# tinyPipes-proto.net
KiCad netlist of a schematic drawn in EAGLE
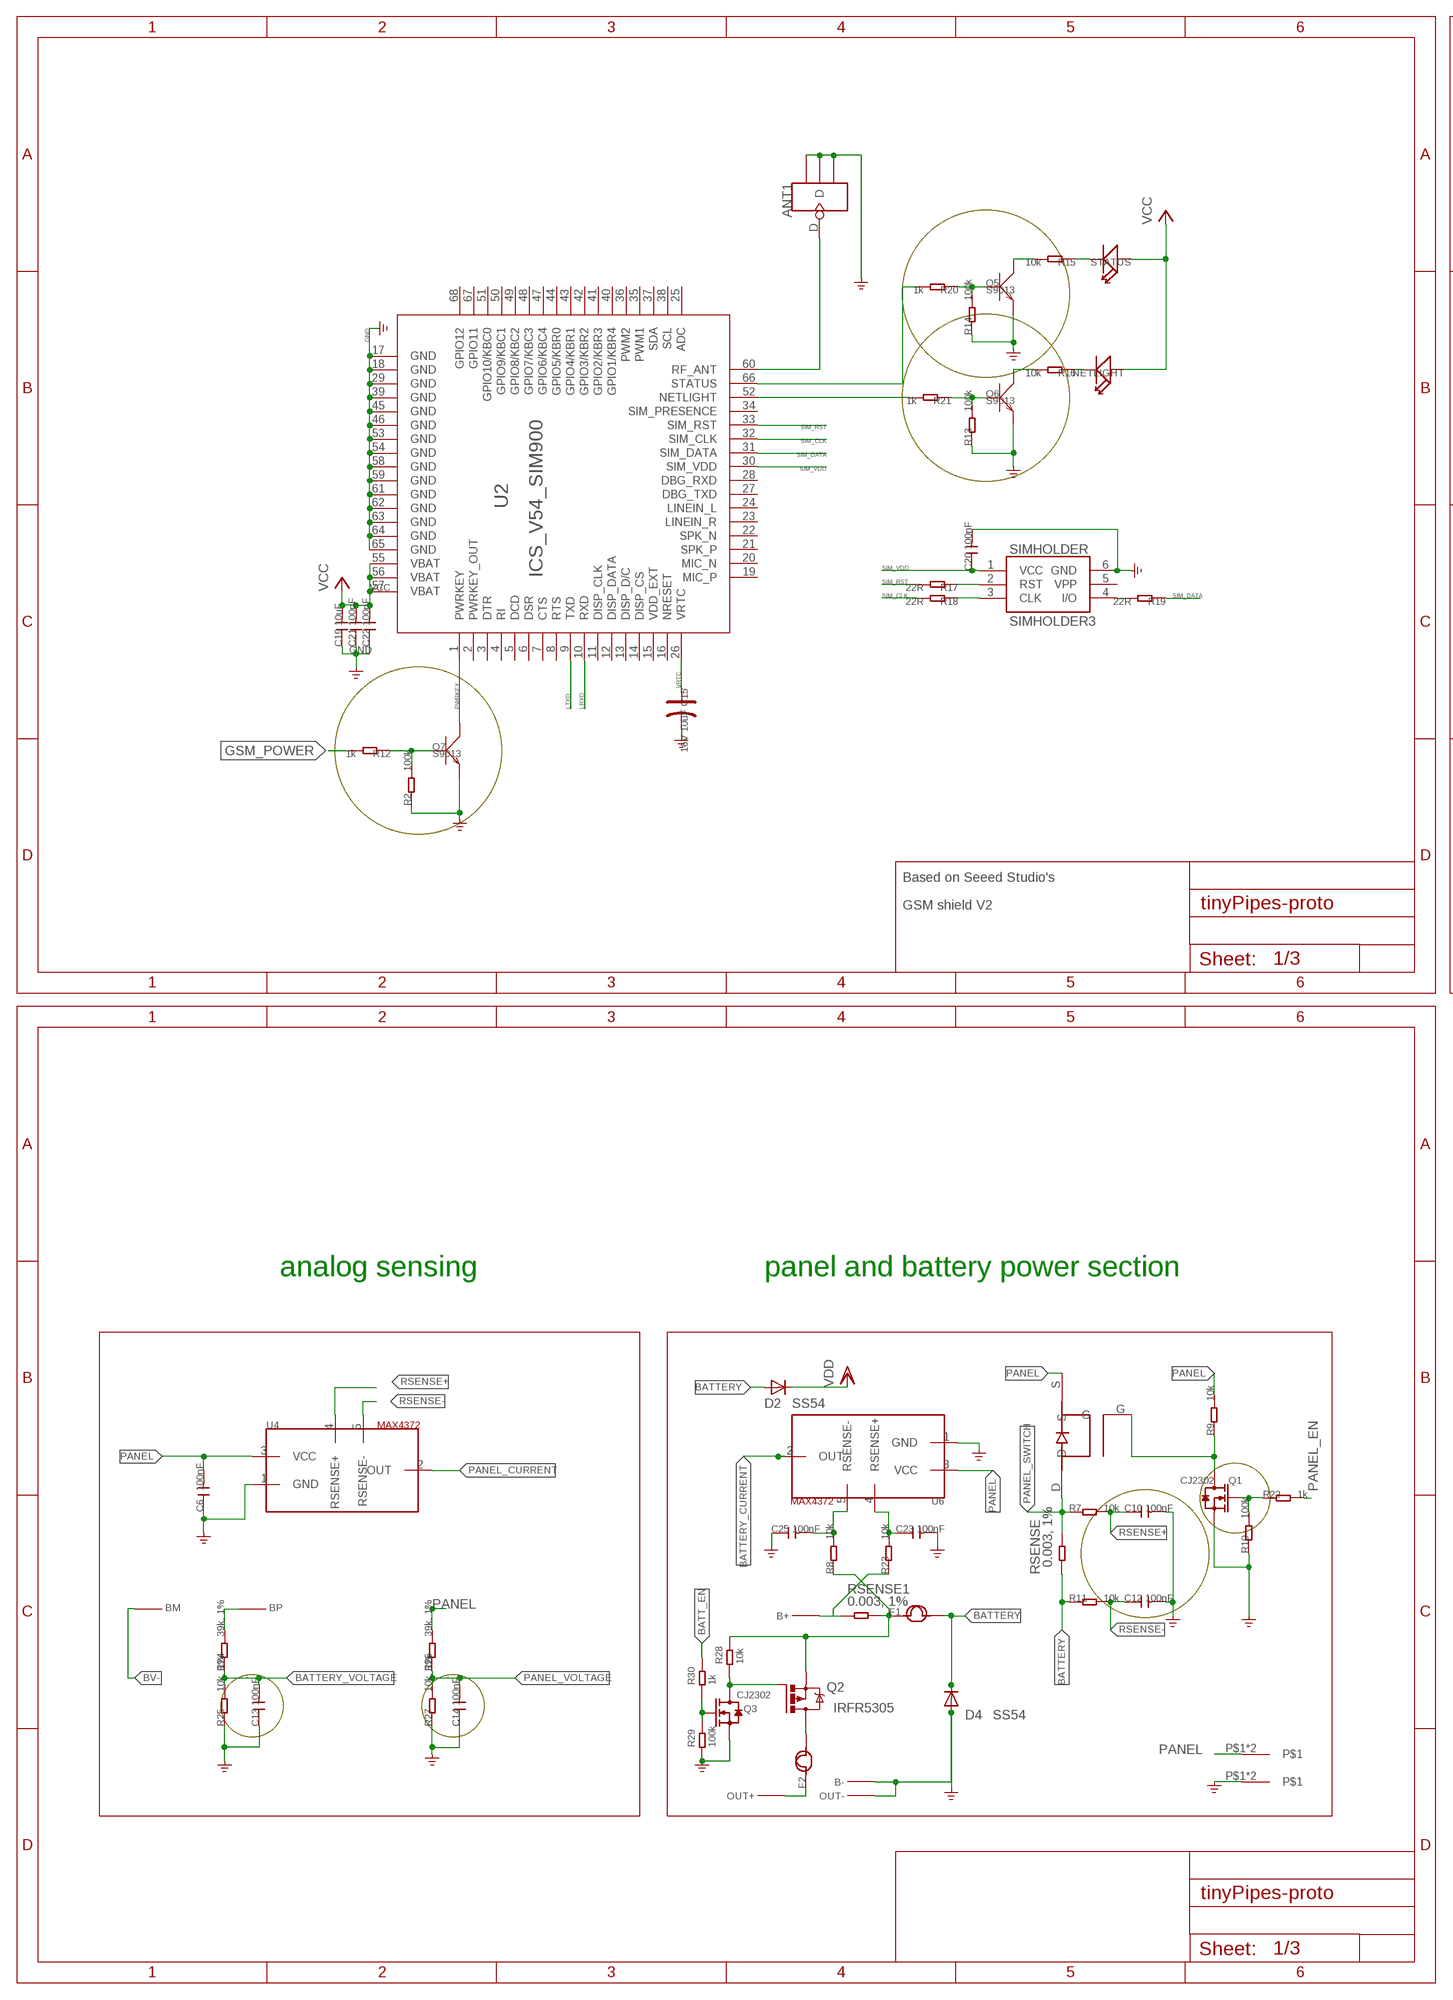
[diagram p0: schematic, sheet 1, part 1 of 2]
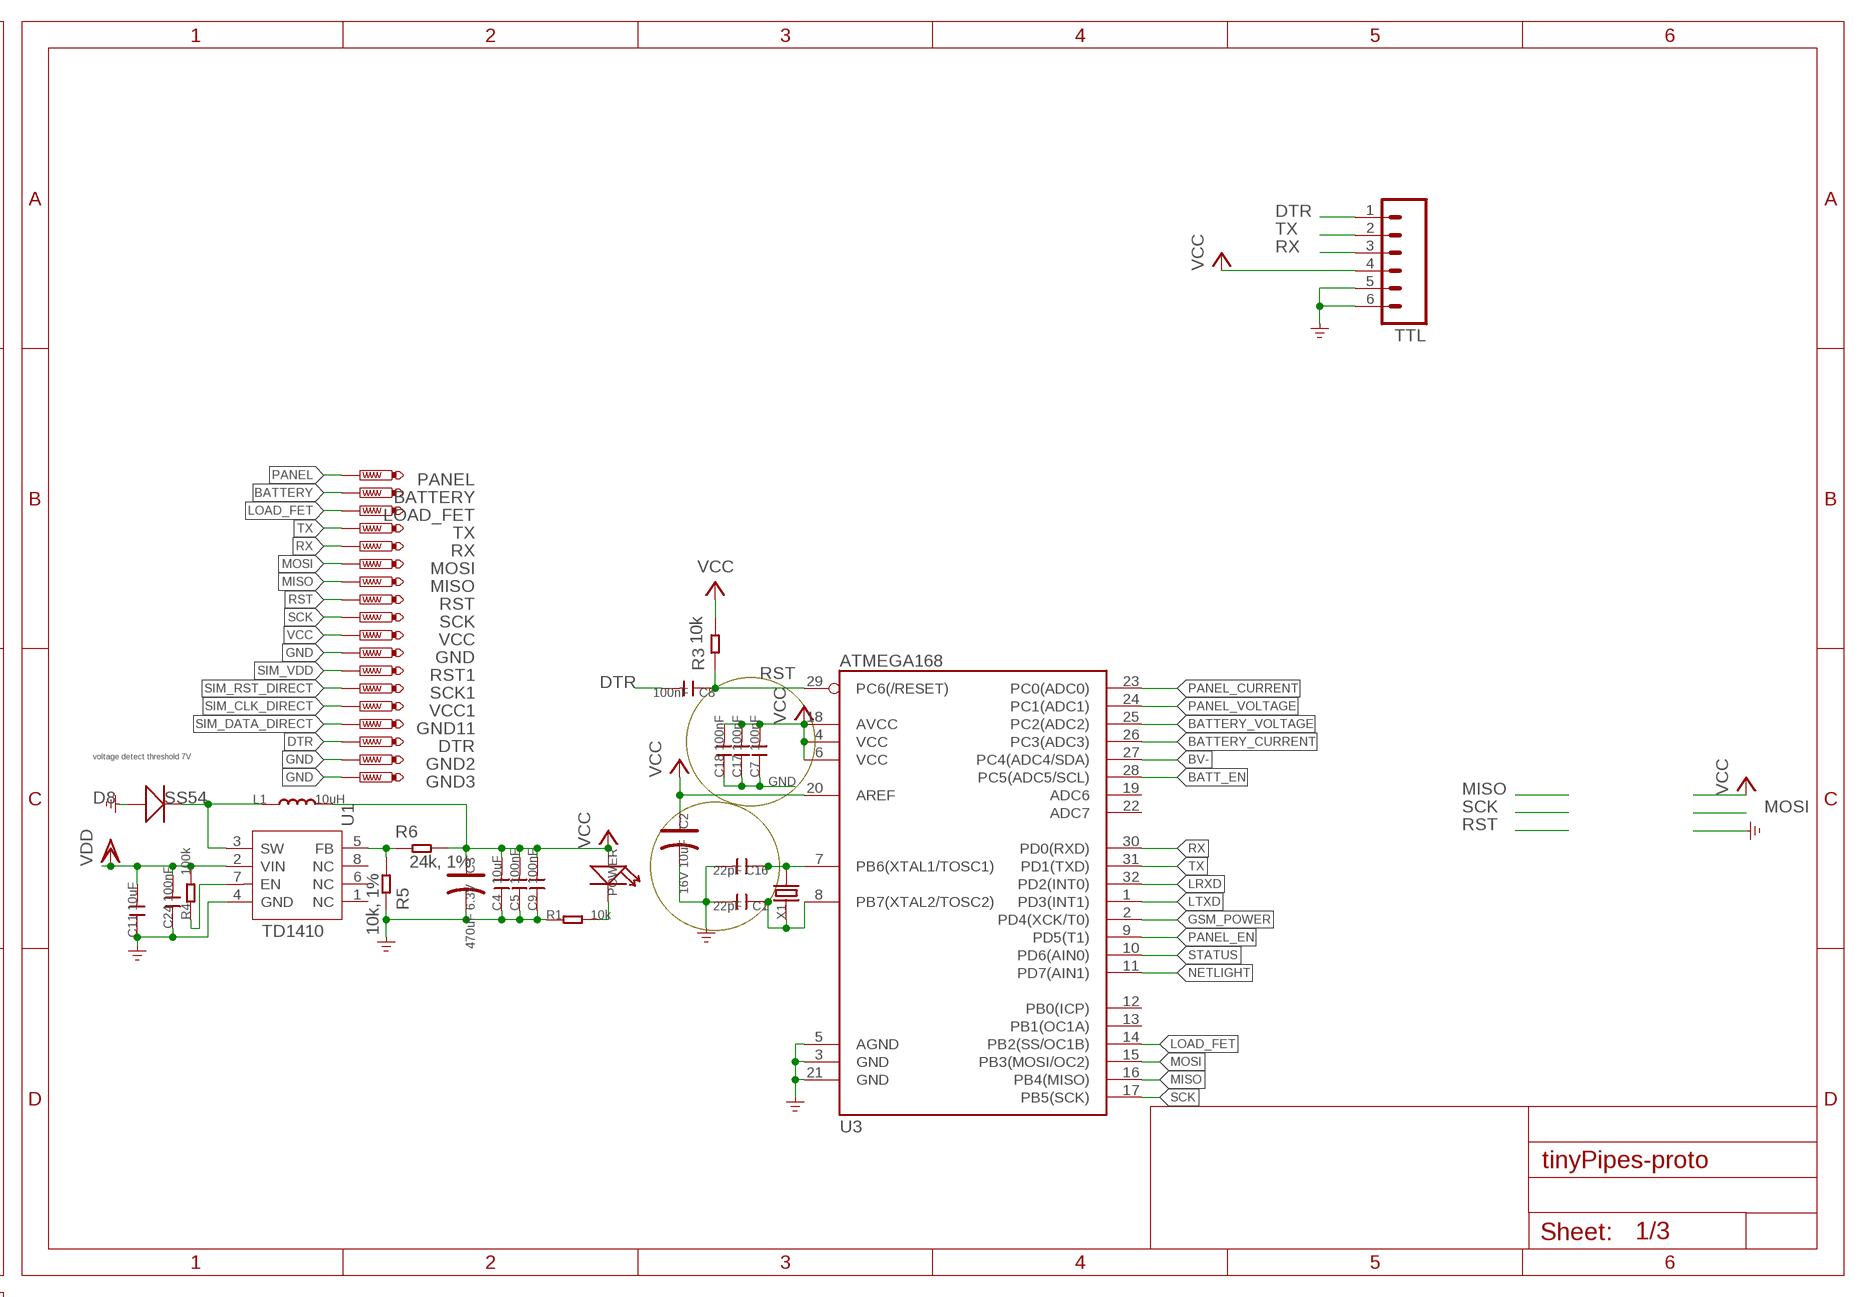
[diagram p1: schematic, sheet 1, part 2 of 2]

(export (version "E")
  (design (tool "Eeschema 10.0.6"))
  (components
    (comp (ref "ANT1")
      (value "ANTENNA-U-FL")
      (footprint "eagle-import:4P-U-FL")
      (libsource (lib "eagle-import") (part "ANTENNA-U-FL"))
    )
    (comp (ref "B+")
      (value "TINYPIPES_BATTBATT")
      (footprint "eagle-import:TINYPIPES_BATT")
      (libsource (lib "eagle-import") (part "TINYPIPES_BATTBATT"))
    )
    (comp (ref "B-")
      (value "TINYPIPES_BATTBATT")
      (footprint "eagle-import:TINYPIPES_BATT")
      (libsource (lib "eagle-import") (part "TINYPIPES_BATTBATT"))
    )
    (comp (ref "BATTERY")
      (value "PTR1B2,54")
      (footprint "eagle-import:B2,54")
      (libsource (lib "eagle-import") (part "PTR1B2,54"))
    )
    (comp (ref "BM")
      (value "TINYPIPES_BATTSBATT")
      (footprint "eagle-import:TINYPIPES_SBATT")
      (libsource (lib "eagle-import") (part "TINYPIPES_BATTSBATT"))
    )
    (comp (ref "BP")
      (value "TINYPIPES_BATTSBATT")
      (footprint "eagle-import:TINYPIPES_SBATT")
      (libsource (lib "eagle-import") (part "TINYPIPES_BATTSBATT"))
    )
    (comp (ref "C1")
      (value "22pF")
      (footprint "eagle-import:C0603")
      (libsource (lib "eagle-import") (part "C-0603"))
    )
    (comp (ref "C2")
      (value "16V 10uF")
      (footprint "eagle-import:AVX-A")
      (libsource (lib "eagle-import") (part "CAP-AVX-A"))
    )
    (comp (ref "C3")
      (value "470uF 6.3V")
      (footprint "eagle-import:AVX-D")
      (libsource (lib "eagle-import") (part "CAP-AVX-D"))
    )
    (comp (ref "C4")
      (value "10uF")
      (footprint "eagle-import:C0805")
      (libsource (lib "eagle-import") (part "C-0805"))
    )
    (comp (ref "C5")
      (value "100nF")
      (footprint "eagle-import:C0603")
      (libsource (lib "eagle-import") (part "C-0603"))
    )
    (comp (ref "C6")
      (value "100nF")
      (footprint "eagle-import:C0603")
      (libsource (lib "eagle-import") (part "C-0603"))
    )
    (comp (ref "C7")
      (value "100nF")
      (footprint "eagle-import:C0603")
      (libsource (lib "eagle-import") (part "C-0603"))
    )
    (comp (ref "C8")
      (value "100nF")
      (footprint "eagle-import:C0603")
      (libsource (lib "eagle-import") (part "C-0603"))
    )
    (comp (ref "C9")
      (value "100nF")
      (footprint "eagle-import:C0603")
      (libsource (lib "eagle-import") (part "C-0603"))
    )
    (comp (ref "C10")
      (value "100nF")
      (footprint "eagle-import:C0805")
      (libsource (lib "eagle-import") (part "C-0805"))
    )
    (comp (ref "C11")
      (value "10uF")
      (footprint "eagle-import:C0805")
      (libsource (lib "eagle-import") (part "C-0805"))
    )
    (comp (ref "C12")
      (value "100nF")
      (footprint "eagle-import:C0805")
      (libsource (lib "eagle-import") (part "C-0805"))
    )
    (comp (ref "C13")
      (value "100nF")
      (footprint "eagle-import:C0603")
      (libsource (lib "eagle-import") (part "C-0603"))
    )
    (comp (ref "C14")
      (value "100nF")
      (footprint "eagle-import:C0603")
      (libsource (lib "eagle-import") (part "C-0603"))
    )
    (comp (ref "C15")
      (value "16V 10uF")
      (footprint "eagle-import:AVX-A")
      (libsource (lib "eagle-import") (part "CAP-AVX-A"))
    )
    (comp (ref "C16")
      (value "22pF")
      (footprint "eagle-import:C0603")
      (libsource (lib "eagle-import") (part "C-0603"))
    )
    (comp (ref "C17")
      (value "100nF")
      (footprint "eagle-import:C0603")
      (libsource (lib "eagle-import") (part "C-0603"))
    )
    (comp (ref "C18")
      (value "100nF")
      (footprint "eagle-import:C0603")
      (libsource (lib "eagle-import") (part "C-0603"))
    )
    (comp (ref "C19")
      (value "10uF")
      (footprint "eagle-import:C0805")
      (libsource (lib "eagle-import") (part "C-0805"))
    )
    (comp (ref "C20")
      (value "100nF")
      (footprint "eagle-import:C0603")
      (libsource (lib "eagle-import") (part "C-0603"))
    )
    (comp (ref "C21")
      (value "100nF")
      (footprint "eagle-import:C0603")
      (libsource (lib "eagle-import") (part "C-0603"))
    )
    (comp (ref "C22")
      (value "100nF")
      (footprint "eagle-import:C0603")
      (libsource (lib "eagle-import") (part "C-0603"))
    )
    (comp (ref "C23")
      (value "100nF")
      (footprint "eagle-import:C0805")
      (libsource (lib "eagle-import") (part "C-0805"))
    )
    (comp (ref "C24")
      (value "100nF")
      (footprint "eagle-import:C0603")
      (libsource (lib "eagle-import") (part "C-0603"))
    )
    (comp (ref "C25")
      (value "100nF")
      (footprint "eagle-import:C0805")
      (libsource (lib "eagle-import") (part "C-0805"))
    )
    (comp (ref "D2")
      (value "SS54")
      (footprint "eagle-import:SMB")
      (libsource (lib "eagle-import") (part "DIODE-SMB"))
    )
    (comp (ref "D4")
      (value "SS54")
      (footprint "eagle-import:SMB")
      (libsource (lib "eagle-import") (part "DIODE-SMB"))
    )
    (comp (ref "D8")
      (value "SS54")
      (footprint "eagle-import:SMB")
      (libsource (lib "eagle-import") (part "D'MBRS240LT3'"))
    )
    (comp (ref "DTR")
      (value "PTR1B2,54")
      (footprint "eagle-import:B2,54")
      (libsource (lib "eagle-import") (part "PTR1B2,54"))
    )
    (comp (ref "F1")
      (value "FUSE16R700")
      (footprint "eagle-import:0210")
      (libsource (lib "eagle-import") (part "FUSE16R700"))
    )
    (comp (ref "F2")
      (value "FUSE16R700")
      (footprint "eagle-import:0210")
      (libsource (lib "eagle-import") (part "FUSE16R700"))
    )
    (comp (ref "GND")
      (value "PTR1B2,54")
      (footprint "eagle-import:B2,54")
      (libsource (lib "eagle-import") (part "PTR1B2,54"))
    )
    (comp (ref "GND2")
      (value "PTR1B2,54")
      (footprint "eagle-import:B2,54")
      (libsource (lib "eagle-import") (part "PTR1B2,54"))
    )
    (comp (ref "GND3")
      (value "PTR1B2,54")
      (footprint "eagle-import:B2,54")
      (libsource (lib "eagle-import") (part "PTR1B2,54"))
    )
    (comp (ref "GND11")
      (value "PTR1B2,54")
      (footprint "eagle-import:B2,54")
      (libsource (lib "eagle-import") (part "PTR1B2,54"))
    )
    (comp (ref "L1")
      (value "10uH")
      (footprint "eagle-import:L0630")
      (libsource (lib "eagle-import") (part "L'0630'"))
    )
    (comp (ref "LOAD_FET")
      (value "PTR1B2,54")
      (footprint "eagle-import:B2,54")
      (libsource (lib "eagle-import") (part "PTR1B2,54"))
    )
    (comp (ref "MISO")
      (value "PTR1B2,54")
      (footprint "eagle-import:B2,54")
      (libsource (lib "eagle-import") (part "PTR1B2,54"))
    )
    (comp (ref "MOSI")
      (value "PTR1B2,54")
      (footprint "eagle-import:B2,54")
      (libsource (lib "eagle-import") (part "PTR1B2,54"))
    )
    (comp (ref "NETLIGHT")
      (value "LED'0603'")
      (footprint "eagle-import:LED-0603")
      (libsource (lib "eagle-import") (part "LED'0603'"))
    )
    (comp (ref "OUT+")
      (value "TINYPIPES_BATTBATT")
      (footprint "eagle-import:TINYPIPES_BATT")
      (libsource (lib "eagle-import") (part "TINYPIPES_BATTBATT"))
    )
    (comp (ref "OUT-")
      (value "TINYPIPES_BATTBATT")
      (footprint "eagle-import:TINYPIPES_BATT")
      (libsource (lib "eagle-import") (part "TINYPIPES_BATTBATT"))
    )
    (comp (ref "PANEL")
      (value "PTR1B2,54")
      (footprint "eagle-import:B2,54")
      (libsource (lib "eagle-import") (part "PTR1B2,54"))
    )
    (comp (ref "PANEL+")
      (value "TINYPIPES_BATTPANEL")
      (footprint "eagle-import:TINYPIPES_PANEL")
      (libsource (lib "eagle-import") (part "tinyPipes_v2.5_TINYPIPES_BATTPANEL"))
    )
    (comp (ref "PANEL-")
      (value "TINYPIPES_BATTPANEL")
      (footprint "eagle-import:TINYPIPES_PANEL")
      (libsource (lib "eagle-import") (part "tinyPipes_v2.5_TINYPIPES_BATTPANEL"))
    )
    (comp (ref "POWER")
      (value "LED'0603'")
      (footprint "eagle-import:LED-0603")
      (libsource (lib "eagle-import") (part "LED'0603'"))
    )
    (comp (ref "Q1")
      (value "CJ2302")
      (footprint "eagle-import:SOT23")
      (libsource (lib "eagle-import") (part "MOSFET-N'SOT23'"))
    )
    (comp (ref "Q2")
      (value "IRFR5305")
      (footprint "eagle-import:D-PAK_TO252AA")
      (libsource (lib "eagle-import") (part "IRF?5305R"))
    )
    (comp (ref "Q3")
      (value "CJ2302")
      (footprint "eagle-import:SOT23")
      (libsource (lib "eagle-import") (part "MOSFET-N'SOT23'"))
    )
    (comp (ref "Q5")
      (value "S9013")
      (footprint "eagle-import:SOT23")
      (libsource (lib "eagle-import") (part "TRANSISTOR-NPN-SOT23"))
    )
    (comp (ref "Q6")
      (value "S9013")
      (footprint "eagle-import:SOT23")
      (libsource (lib "eagle-import") (part "TRANSISTOR-NPN-SOT23"))
    )
    (comp (ref "Q7")
      (value "S9013")
      (footprint "eagle-import:SOT23")
      (libsource (lib "eagle-import") (part "TRANSISTOR-NPN-SOT23"))
    )
    (comp (ref "R1")
      (value "10k")
      (footprint "eagle-import:R0603")
      (libsource (lib "eagle-import") (part "R-0603"))
    )
    (comp (ref "R2")
      (value "100k")
      (footprint "eagle-import:R0603")
      (libsource (lib "eagle-import") (part "R-0603"))
    )
    (comp (ref "R3")
      (value "10k")
      (footprint "eagle-import:R0603")
      (libsource (lib "eagle-import") (part "R-0603"))
    )
    (comp (ref "R4")
      (value "100k")
      (footprint "eagle-import:R0603")
      (libsource (lib "eagle-import") (part "R-0603"))
    )
    (comp (ref "R5")
      (value "10k, 1%")
      (footprint "eagle-import:R0603")
      (libsource (lib "eagle-import") (part "R-0603"))
    )
    (comp (ref "R6")
      (value "24k, 1%")
      (footprint "eagle-import:R0603")
      (libsource (lib "eagle-import") (part "R-0603"))
    )
    (comp (ref "R7")
      (value "10k")
      (footprint "eagle-import:R0603")
      (libsource (lib "eagle-import") (part "R-0603"))
    )
    (comp (ref "R8")
      (value "10k")
      (footprint "eagle-import:R0603")
      (libsource (lib "eagle-import") (part "R-0603"))
    )
    (comp (ref "R9")
      (value "10k")
      (footprint "eagle-import:R0603")
      (libsource (lib "eagle-import") (part "R-0603"))
    )
    (comp (ref "R10")
      (value "100k")
      (footprint "eagle-import:R0603")
      (libsource (lib "eagle-import") (part "R-0603"))
    )
    (comp (ref "R11")
      (value "10k")
      (footprint "eagle-import:R0603")
      (libsource (lib "eagle-import") (part "R-0603"))
    )
    (comp (ref "R12")
      (value "1k")
      (footprint "eagle-import:R0603")
      (libsource (lib "eagle-import") (part "R-0603"))
    )
    (comp (ref "R13")
      (value "100k")
      (footprint "eagle-import:R0603")
      (libsource (lib "eagle-import") (part "R-0603"))
    )
    (comp (ref "R14")
      (value "100k")
      (footprint "eagle-import:R0603")
      (libsource (lib "eagle-import") (part "R-0603"))
    )
    (comp (ref "R15")
      (value "10k")
      (footprint "eagle-import:R0603")
      (libsource (lib "eagle-import") (part "R-0603"))
    )
    (comp (ref "R16")
      (value "10k")
      (footprint "eagle-import:R0603")
      (libsource (lib "eagle-import") (part "R-0603"))
    )
    (comp (ref "R17")
      (value "22R")
      (footprint "eagle-import:R0603")
      (libsource (lib "eagle-import") (part "R-0603"))
    )
    (comp (ref "R18")
      (value "22R")
      (footprint "eagle-import:R0603")
      (libsource (lib "eagle-import") (part "R-0603"))
    )
    (comp (ref "R19")
      (value "22R")
      (footprint "eagle-import:R0603")
      (libsource (lib "eagle-import") (part "R-0603"))
    )
    (comp (ref "R20")
      (value "1k")
      (footprint "eagle-import:R0603")
      (libsource (lib "eagle-import") (part "R-0603"))
    )
    (comp (ref "R21")
      (value "1k")
      (footprint "eagle-import:R0603")
      (libsource (lib "eagle-import") (part "R-0603"))
    )
    (comp (ref "R22")
      (value "1k")
      (footprint "eagle-import:R0603")
      (libsource (lib "eagle-import") (part "R-0603"))
    )
    (comp (ref "R23")
      (value "10k")
      (footprint "eagle-import:R0603")
      (libsource (lib "eagle-import") (part "R-0603"))
    )
    (comp (ref "R24")
      (value "39k, 1%")
      (footprint "eagle-import:R0603")
      (libsource (lib "eagle-import") (part "R-0603"))
    )
    (comp (ref "R25")
      (value "10k, 1%")
      (footprint "eagle-import:R0603")
      (libsource (lib "eagle-import") (part "R-0603"))
    )
    (comp (ref "R26")
      (value "39k, 1%")
      (footprint "eagle-import:R0603")
      (libsource (lib "eagle-import") (part "R-0603"))
    )
    (comp (ref "R27")
      (value "10k, 1%")
      (footprint "eagle-import:R0603")
      (libsource (lib "eagle-import") (part "R-0603"))
    )
    (comp (ref "R28")
      (value "10k")
      (footprint "eagle-import:R0603")
      (libsource (lib "eagle-import") (part "R-0603"))
    )
    (comp (ref "R29")
      (value "100k")
      (footprint "eagle-import:R0603")
      (libsource (lib "eagle-import") (part "R-0603"))
    )
    (comp (ref "R30")
      (value "1k")
      (footprint "eagle-import:R0603")
      (libsource (lib "eagle-import") (part "R-0603"))
    )
    (comp (ref "RSENSE")
      (value "0.003, 1%")
      (footprint "eagle-import:R2512")
      (libsource (lib "eagle-import") (part "R-2512"))
    )
    (comp (ref "RSENSE1")
      (value "0.003, 1%")
      (footprint "eagle-import:R2512")
      (libsource (lib "eagle-import") (part "R-2512"))
    )
    (comp (ref "RST")
      (value "PTR1B2,54")
      (footprint "eagle-import:B2,54")
      (libsource (lib "eagle-import") (part "PTR1B2,54"))
    )
    (comp (ref "RST1")
      (value "PTR1B2,54")
      (footprint "eagle-import:B2,54")
      (libsource (lib "eagle-import") (part "PTR1B2,54"))
    )
    (comp (ref "RX")
      (value "PTR1B2,54")
      (footprint "eagle-import:B2,54")
      (libsource (lib "eagle-import") (part "PTR1B2,54"))
    )
    (comp (ref "SCK")
      (value "PTR1B2,54")
      (footprint "eagle-import:B2,54")
      (libsource (lib "eagle-import") (part "PTR1B2,54"))
    )
    (comp (ref "SCK1")
      (value "PTR1B2,54")
      (footprint "eagle-import:B2,54")
      (libsource (lib "eagle-import") (part "PTR1B2,54"))
    )
    (comp (ref "SIMHOLDER")
      (value "SIMHOLDER3")
      (footprint "eagle-import:SIMHOLDER3")
      (libsource (lib "eagle-import") (part "SIMHOLDER3"))
    )
    (comp (ref "STATUS")
      (value "LED'0603'")
      (footprint "eagle-import:LED-0603")
      (libsource (lib "eagle-import") (part "LED'0603'"))
    )
    (comp (ref "TTL")
      (value "M06LOCK")
      (footprint "eagle-import:1X06_LOCK")
      (libsource (lib "eagle-import") (part "M06LOCK"))
    )
    (comp (ref "TX")
      (value "PTR1B2,54")
      (footprint "eagle-import:B2,54")
      (libsource (lib "eagle-import") (part "PTR1B2,54"))
    )
    (comp (ref "U1")
      (value "TD1410")
      (footprint "eagle-import:SOP8")
      (libsource (lib "eagle-import") (part "TD1410"))
    )
    (comp (ref "U2")
      (value "ICS_V54_SIM900")
      (footprint "eagle-import:ICS_V54_SIM900")
      (libsource (lib "eagle-import") (part "ICS_V54_SIM900"))
    )
    (comp (ref "U3")
      (value "ATMEGA168")
      (footprint "eagle-import:TQFP32-08")
      (libsource (lib "eagle-import") (part "ATMEGA168"))
    )
    (comp (ref "U4")
      (value "MAX4372")
      (footprint "eagle-import:SOT23-5")
      (libsource (lib "eagle-import") (part "MAX4372"))
    )
    (comp (ref "U5")
      (value "SI4435POWER")
      (footprint "eagle-import:SO8_FET")
      (libsource (lib "eagle-import") (part "SI4435POWER"))
    )
    (comp (ref "U6")
      (value "MAX4372")
      (footprint "eagle-import:SOT23-5")
      (libsource (lib "eagle-import") (part "MAX4372"))
    )
    (comp (ref "VCC")
      (value "PTR1B2,54")
      (footprint "eagle-import:B2,54")
      (libsource (lib "eagle-import") (part "PTR1B2,54"))
    )
    (comp (ref "VCC1")
      (value "PTR1B2,54")
      (footprint "eagle-import:B2,54")
      (libsource (lib "eagle-import") (part "PTR1B2,54"))
    )
    (comp (ref "X1")
      (value "CRYSTAL'5032'")
      (footprint "eagle-import:2P-SMD-5X3.2")
      (libsource (lib "eagle-import") (part "CRYSTAL'5032'"))
    )
  )
  (nets
    (net (code "1") (name "BATTERY") (class "Default")
      (node (ref "BATTERY") (pin "TP") (pinfunction "TP_TP") (pintype "input"))
      (node (ref "D2") (pin "A") (pinfunction "A_A") (pintype "passive"))
      (node (ref "D4") (pin "C") (pinfunction "C_C") (pintype "passive"))
      (node (ref "F1") (pin "2") (pinfunction "2_2") (pintype "bidirectional"))
      (node (ref "R11") (pin "1") (pinfunction "1_1") (pintype "passive"))
      (node (ref "RSENSE") (pin "1") (pinfunction "1_1") (pintype "passive"))
    )
    (net (code "2") (name "BATTERY_CURRENT") (class "Default")
      (node (ref "U3") (pin "26") (pinfunction "PC3(ADC3)_26") (pintype "bidirectional"))
      (node (ref "U6") (pin "2") (pinfunction "OUT_2") (pintype "bidirectional"))
    )
    (net (code "3") (name "BATTERY_VOLTAGE") (class "Default")
      (node (ref "C13") (pin "2") (pinfunction "2_2") (pintype "passive"))
      (node (ref "R24") (pin "1") (pinfunction "1_1") (pintype "passive"))
      (node (ref "R25") (pin "2") (pinfunction "2_2") (pintype "passive"))
      (node (ref "U3") (pin "25") (pinfunction "PC2(ADC2)_25") (pintype "bidirectional"))
    )
    (net (code "4") (name "BATT_EN") (class "Default")
      (node (ref "R30") (pin "2") (pinfunction "2_2") (pintype "passive"))
      (node (ref "U3") (pin "28") (pinfunction "PC5(ADC5/SCL)_28") (pintype "bidirectional"))
    )
    (net (code "5") (name "BV-") (class "Default")
      (node (ref "BM") (pin "P$1") (pinfunction "P$1_P$1") (pintype "bidirectional"))
      (node (ref "U3") (pin "27") (pinfunction "PC4(ADC4/SDA)_27") (pintype "bidirectional"))
    )
    (net (code "6") (name "DTR") (class "Default")
      (node (ref "C8") (pin "2") (pinfunction "2_2") (pintype "passive"))
      (node (ref "DTR") (pin "TP") (pinfunction "TP_TP") (pintype "input"))
      (node (ref "TTL") (pin "1") (pinfunction "1_1") (pintype "passive"))
    )
    (net (code "7") (name "GND") (class "Default")
      (node (ref "ANT1") (pin "GND1") (pinfunction "GND1_GND1") (pintype "bidirectional"))
      (node (ref "ANT1") (pin "GND2") (pinfunction "GND2_GND2") (pintype "bidirectional"))
      (node (ref "ANT1") (pin "GND3") (pinfunction "GND3_GND3") (pintype "bidirectional"))
      (node (ref "B-") (pin "1") (pinfunction "P$1_1") (pintype "bidirectional"))
      (node (ref "C1") (pin "2") (pinfunction "2_2") (pintype "passive"))
      (node (ref "C10") (pin "2") (pinfunction "2_2") (pintype "passive"))
      (node (ref "C11") (pin "1") (pinfunction "1_1") (pintype "passive"))
      (node (ref "C12") (pin "2") (pinfunction "2_2") (pintype "passive"))
      (node (ref "C13") (pin "1") (pinfunction "1_1") (pintype "passive"))
      (node (ref "C14") (pin "1") (pinfunction "1_1") (pintype "passive"))
      (node (ref "C15") (pin "-") (pinfunction "-_-") (pintype "passive"))
      (node (ref "C16") (pin "2") (pinfunction "2_2") (pintype "passive"))
      (node (ref "C17") (pin "1") (pinfunction "1_1") (pintype "passive"))
      (node (ref "C18") (pin "1") (pinfunction "1_1") (pintype "passive"))
      (node (ref "C19") (pin "1") (pinfunction "1_1") (pintype "passive"))
      (node (ref "C2") (pin "-") (pinfunction "-_-") (pintype "passive"))
      (node (ref "C20") (pin "2") (pinfunction "2_2") (pintype "passive"))
      (node (ref "C21") (pin "1") (pinfunction "1_1") (pintype "passive"))
      (node (ref "C22") (pin "1") (pinfunction "1_1") (pintype "passive"))
      (node (ref "C23") (pin "2") (pinfunction "2_2") (pintype "passive"))
      (node (ref "C24") (pin "1") (pinfunction "1_1") (pintype "passive"))
      (node (ref "C25") (pin "1") (pinfunction "1_1") (pintype "passive"))
      (node (ref "C3") (pin "-") (pinfunction "-_-") (pintype "passive"))
      (node (ref "C4") (pin "1") (pinfunction "1_1") (pintype "passive"))
      (node (ref "C5") (pin "1") (pinfunction "1_1") (pintype "passive"))
      (node (ref "C6") (pin "1") (pinfunction "1_1") (pintype "passive"))
      (node (ref "C7") (pin "1") (pinfunction "1_1") (pintype "passive"))
      (node (ref "C9") (pin "1") (pinfunction "1_1") (pintype "passive"))
      (node (ref "D4") (pin "A") (pinfunction "A_A") (pintype "passive"))
      (node (ref "D8") (pin "+") (pinfunction "+_+") (pintype "passive"))
      (node (ref "GND") (pin "TP") (pinfunction "TP_TP") (pintype "input"))
      (node (ref "GND2") (pin "TP") (pinfunction "TP_TP") (pintype "input"))
      (node (ref "GND3") (pin "TP") (pinfunction "TP_TP") (pintype "input"))
      (node (ref "OUT-") (pin "1") (pinfunction "P$1_1") (pintype "bidirectional"))
      (node (ref "PANEL-") (pin "P$1") (pinfunction "P$1_P$1") (pintype "bidirectional"))
      (node (ref "PANEL-") (pin "P$2") (pinfunction "P$1_P$2") (pintype "bidirectional"))
      (node (ref "Q1") (pin "2") (pinfunction "S_2") (pintype "passive"))
      (node (ref "Q3") (pin "2") (pinfunction "S_2") (pintype "passive"))
      (node (ref "Q5") (pin "2") (pinfunction "E_2") (pintype "passive"))
      (node (ref "Q6") (pin "2") (pinfunction "E_2") (pintype "passive"))
      (node (ref "Q7") (pin "2") (pinfunction "E_2") (pintype "passive"))
      (node (ref "R1") (pin "1") (pinfunction "1_1") (pintype "passive"))
      (node (ref "R10") (pin "1") (pinfunction "1_1") (pintype "passive"))
      (node (ref "R13") (pin "1") (pinfunction "1_1") (pintype "passive"))
      (node (ref "R14") (pin "1") (pinfunction "1_1") (pintype "passive"))
      (node (ref "R2") (pin "1") (pinfunction "1_1") (pintype "passive"))
      (node (ref "R25") (pin "1") (pinfunction "1_1") (pintype "passive"))
      (node (ref "R27") (pin "1") (pinfunction "1_1") (pintype "passive"))
      (node (ref "R29") (pin "1") (pinfunction "1_1") (pintype "passive"))
      (node (ref "R5") (pin "2") (pinfunction "2_2") (pintype "passive"))
      (node (ref "SIMHOLDER") (pin "6") (pinfunction "GND_6") (pintype "bidirectional"))
      (node (ref "TTL") (pin "5") (pinfunction "5_5") (pintype "passive"))
      (node (ref "TTL") (pin "6") (pinfunction "6_6") (pintype "passive"))
      (node (ref "U1") (pin "4") (pinfunction "GND_4") (pintype "power_in"))
      (node (ref "U2") (pin "17") (pinfunction "GND_17") (pintype "power_in"))
      (node (ref "U2") (pin "18") (pinfunction "GND_18") (pintype "power_in"))
      (node (ref "U2") (pin "29") (pinfunction "GND_29") (pintype "power_in"))
      (node (ref "U2") (pin "39") (pinfunction "GND_39") (pintype "power_in"))
      (node (ref "U2") (pin "45") (pinfunction "GND_45") (pintype "power_in"))
      (node (ref "U2") (pin "46") (pinfunction "GND_46") (pintype "power_in"))
      (node (ref "U2") (pin "53") (pinfunction "GND_53") (pintype "power_in"))
      (node (ref "U2") (pin "54") (pinfunction "GND_54") (pintype "power_in"))
      (node (ref "U2") (pin "58") (pinfunction "GND_58") (pintype "power_in"))
      (node (ref "U2") (pin "59") (pinfunction "GND_59") (pintype "power_in"))
      (node (ref "U2") (pin "61") (pinfunction "GND_61") (pintype "power_in"))
      (node (ref "U2") (pin "62") (pinfunction "GND_62") (pintype "power_in"))
      (node (ref "U2") (pin "63") (pinfunction "GND_63") (pintype "power_in"))
      (node (ref "U2") (pin "64") (pinfunction "GND_64") (pintype "power_in"))
      (node (ref "U2") (pin "65") (pinfunction "GND_65") (pintype "power_in"))
      (node (ref "U3") (pin "21") (pinfunction "GND_21") (pintype "bidirectional"))
      (node (ref "U3") (pin "3") (pinfunction "GND_3") (pintype "bidirectional"))
      (node (ref "U3") (pin "5") (pinfunction "AGND_5") (pintype "bidirectional"))
      (node (ref "U4") (pin "1") (pinfunction "GND_1") (pintype "bidirectional"))
      (node (ref "U6") (pin "1") (pinfunction "GND_1") (pintype "bidirectional"))
    )
    (net (code "8") (name "GSM_POWER") (class "Default")
      (node (ref "R12") (pin "2") (pinfunction "2_2") (pintype "passive"))
      (node (ref "U3") (pin "2") (pinfunction "PD4(XCK/T0)_2") (pintype "bidirectional"))
    )
    (net (code "9") (name "LOAD_FET") (class "Default")
      (node (ref "LOAD_FET") (pin "TP") (pinfunction "TP_TP") (pintype "input"))
      (node (ref "U3") (pin "14") (pinfunction "PB2(SS/OC1B)_14") (pintype "bidirectional"))
    )
    (net (code "10") (name "LRXD") (class "Default")
      (node (ref "U2") (pin "10") (pinfunction "RXD_10") (pintype "input"))
      (node (ref "U3") (pin "32") (pinfunction "PD2(INT0)_32") (pintype "bidirectional"))
    )
    (net (code "11") (name "LTXD") (class "Default")
      (node (ref "U2") (pin "9") (pinfunction "TXD_9") (pintype "output"))
      (node (ref "U3") (pin "1") (pinfunction "PD3(INT1)_1") (pintype "bidirectional"))
    )
    (net (code "12") (name "MISO") (class "Default")
      (node (ref "MISO") (pin "TP") (pinfunction "TP_TP") (pintype "input"))
      (node (ref "U3") (pin "16") (pinfunction "PB4(MISO)_16") (pintype "bidirectional"))
    )
    (net (code "13") (name "MOSI") (class "Default")
      (node (ref "MOSI") (pin "TP") (pinfunction "TP_TP") (pintype "input"))
      (node (ref "U3") (pin "15") (pinfunction "PB3(MOSI/OC2)_15") (pintype "bidirectional"))
    )
    (net (code "14") (name "NETLIGHT") (class "Default")
      (node (ref "R21") (pin "2") (pinfunction "2_2") (pintype "passive"))
      (node (ref "U2") (pin "52") (pinfunction "NETLIGHT_52") (pintype "output"))
      (node (ref "U3") (pin "11") (pinfunction "PD7(AIN1)_11") (pintype "bidirectional"))
    )
    (net (code "15") (name "Net-(B+-P$1)") (class "Default")
      (node (ref "B+") (pin "1") (pinfunction "P$1_1") (pintype "bidirectional"))
      (node (ref "R23") (pin "1") (pinfunction "1_1") (pintype "passive"))
      (node (ref "RSENSE1") (pin "1") (pinfunction "1_1") (pintype "passive"))
    )
    (net (code "16") (name "Net-(BP-PadP$1)") (class "Default")
      (node (ref "BP") (pin "P$1") (pinfunction "P$1_P$1") (pintype "bidirectional"))
      (node (ref "R24") (pin "2") (pinfunction "2_2") (pintype "passive"))
    )
    (net (code "17") (name "Net-(NETLIGHT-Pad-)") (class "Default")
      (node (ref "NETLIGHT") (pin "-") (pinfunction "-_-") (pintype "passive"))
      (node (ref "R16") (pin "1") (pinfunction "1_1") (pintype "passive"))
    )
    (net (code "18") (name "Net-(OUT+-P$1)") (class "Default")
      (node (ref "F2") (pin "1") (pinfunction "1_1") (pintype "bidirectional"))
      (node (ref "OUT+") (pin "1") (pinfunction "P$1_1") (pintype "bidirectional"))
    )
    (net (code "19") (name "Net-(POWER-Pad-)") (class "Default")
      (node (ref "POWER") (pin "-") (pinfunction "-_-") (pintype "passive"))
      (node (ref "R1") (pin "2") (pinfunction "2_2") (pintype "passive"))
    )
    (net (code "20") (name "Net-(Q1-D)") (class "Default")
      (node (ref "Q1") (pin "3") (pinfunction "D_3") (pintype "passive"))
      (node (ref "R9") (pin "1") (pinfunction "1_1") (pintype "passive"))
      (node (ref "U5") (pin "G") (pinfunction "G_G") (pintype "bidirectional"))
    )
    (net (code "21") (name "Net-(Q1-G)") (class "Default")
      (node (ref "Q1") (pin "1") (pinfunction "G_1") (pintype "passive"))
      (node (ref "R10") (pin "2") (pinfunction "2_2") (pintype "passive"))
      (node (ref "R22") (pin "1") (pinfunction "1_1") (pintype "passive"))
    )
    (net (code "22") (name "Net-(Q2-D)") (class "Default")
      (node (ref "F2") (pin "2") (pinfunction "2_2") (pintype "bidirectional"))
      (node (ref "Q2") (pin "4") (pinfunction "D_4") (pintype "passive"))
    )
    (net (code "23") (name "Net-(Q2-G)") (class "Default")
      (node (ref "Q2") (pin "1") (pinfunction "G_1") (pintype "passive"))
      (node (ref "Q3") (pin "3") (pinfunction "D_3") (pintype "passive"))
      (node (ref "R28") (pin "1") (pinfunction "1_1") (pintype "passive"))
    )
    (net (code "24") (name "Net-(Q2-S)") (class "Default")
      (node (ref "F1") (pin "1") (pinfunction "1_1") (pintype "bidirectional"))
      (node (ref "Q2") (pin "3") (pinfunction "S_3") (pintype "passive"))
      (node (ref "R28") (pin "2") (pinfunction "2_2") (pintype "passive"))
      (node (ref "R8") (pin "1") (pinfunction "1_1") (pintype "passive"))
      (node (ref "RSENSE1") (pin "2") (pinfunction "2_2") (pintype "passive"))
    )
    (net (code "25") (name "Net-(Q3-G)") (class "Default")
      (node (ref "Q3") (pin "1") (pinfunction "G_1") (pintype "passive"))
      (node (ref "R29") (pin "2") (pinfunction "2_2") (pintype "passive"))
      (node (ref "R30") (pin "1") (pinfunction "1_1") (pintype "passive"))
    )
    (net (code "26") (name "Net-(Q5-B)") (class "Default")
      (node (ref "Q5") (pin "1") (pinfunction "B_1") (pintype "passive"))
      (node (ref "R14") (pin "2") (pinfunction "2_2") (pintype "passive"))
      (node (ref "R20") (pin "1") (pinfunction "1_1") (pintype "passive"))
    )
    (net (code "27") (name "Net-(Q5-C)") (class "Default")
      (node (ref "Q5") (pin "3") (pinfunction "C_3") (pintype "passive"))
      (node (ref "R15") (pin "2") (pinfunction "2_2") (pintype "passive"))
    )
    (net (code "28") (name "Net-(Q6-B)") (class "Default")
      (node (ref "Q6") (pin "1") (pinfunction "B_1") (pintype "passive"))
      (node (ref "R13") (pin "2") (pinfunction "2_2") (pintype "passive"))
      (node (ref "R21") (pin "1") (pinfunction "1_1") (pintype "passive"))
    )
    (net (code "29") (name "Net-(Q6-C)") (class "Default")
      (node (ref "Q6") (pin "3") (pinfunction "C_3") (pintype "passive"))
      (node (ref "R16") (pin "2") (pinfunction "2_2") (pintype "passive"))
    )
    (net (code "30") (name "Net-(Q7-B)") (class "Default")
      (node (ref "Q7") (pin "1") (pinfunction "B_1") (pintype "passive"))
      (node (ref "R12") (pin "1") (pinfunction "1_1") (pintype "passive"))
      (node (ref "R2") (pin "2") (pinfunction "2_2") (pintype "passive"))
    )
    (net (code "31") (name "Net-(R15-Pad1)") (class "Default")
      (node (ref "R15") (pin "1") (pinfunction "1_1") (pintype "passive"))
      (node (ref "STATUS") (pin "-") (pinfunction "-_-") (pintype "passive"))
    )
    (net (code "32") (name "Net-(U1-EN)") (class "Default")
      (node (ref "R4") (pin "1") (pinfunction "1_1") (pintype "passive"))
      (node (ref "U1") (pin "7") (pinfunction "EN_7") (pintype "input"))
    )
    (net (code "33") (name "Net-(U1-FB)") (class "Default")
      (node (ref "R5") (pin "1") (pinfunction "1_1") (pintype "passive"))
      (node (ref "R6") (pin "1") (pinfunction "1_1") (pintype "passive"))
      (node (ref "U1") (pin "5") (pinfunction "FB_5") (pintype "input"))
    )
    (net (code "34") (name "Net-(U1-SW)") (class "Default")
      (node (ref "D8") (pin "-") (pinfunction "-_-") (pintype "passive"))
      (node (ref "L1") (pin "1") (pinfunction "1_1") (pintype "passive"))
      (node (ref "U1") (pin "3") (pinfunction "SW_3") (pintype "output"))
    )
    (net (code "35") (name "Net-(U2-RF_ANT)") (class "Default")
      (node (ref "ANT1") (pin "D") (pinfunction "D_D") (pintype "bidirectional"))
      (node (ref "U2") (pin "60") (pinfunction "RF_ANT_60") (pintype "bidirectional"))
    )
    (net (code "36") (name "Net-(U3-PB6(XTAL1{slash}TOSC1))") (class "Default")
      (node (ref "C16") (pin "1") (pinfunction "1_1") (pintype "passive"))
      (node (ref "U3") (pin "7") (pinfunction "PB6(XTAL1/TOSC1)_7") (pintype "bidirectional"))
      (node (ref "X1") (pin "2") (pinfunction "2_2") (pintype "passive"))
    )
    (net (code "37") (name "Net-(U3-PB7(XTAL2{slash}TOSC2))") (class "Default")
      (node (ref "C1") (pin "1") (pinfunction "1_1") (pintype "passive"))
      (node (ref "U3") (pin "8") (pinfunction "PB7(XTAL2/TOSC2)_8") (pintype "bidirectional"))
      (node (ref "X1") (pin "1") (pinfunction "1_1") (pintype "passive"))
    )
    (net (code "38") (name "Net-(U6-RSENSE+)") (class "Default")
      (node (ref "C23") (pin "1") (pinfunction "1_1") (pintype "passive"))
      (node (ref "R23") (pin "2") (pinfunction "2_2") (pintype "passive"))
      (node (ref "U6") (pin "4") (pinfunction "RSENSE+_4") (pintype "bidirectional"))
    )
    (net (code "39") (name "Net-(U6-RSENSE-)") (class "Default")
      (node (ref "C25") (pin "2") (pinfunction "2_2") (pintype "passive"))
      (node (ref "R8") (pin "2") (pinfunction "2_2") (pintype "passive"))
      (node (ref "U6") (pin "5") (pinfunction "RSENSE-_5") (pintype "bidirectional"))
    )
    (net (code "40") (name "PANEL") (class "Default")
      (node (ref "C6") (pin "2") (pinfunction "2_2") (pintype "passive"))
      (node (ref "PANEL") (pin "TP") (pinfunction "TP_TP") (pintype "input"))
      (node (ref "PANEL+") (pin "P$1") (pinfunction "P$1_P$1") (pintype "bidirectional"))
      (node (ref "PANEL+") (pin "P$2") (pinfunction "P$1_P$2") (pintype "bidirectional"))
      (node (ref "R26") (pin "2") (pinfunction "2_2") (pintype "passive"))
      (node (ref "R9") (pin "2") (pinfunction "2_2") (pintype "passive"))
      (node (ref "U4") (pin "3") (pinfunction "VCC_3") (pintype "bidirectional"))
      (node (ref "U5") (pin "S") (pinfunction "S_S") (pintype "bidirectional"))
      (node (ref "U6") (pin "3") (pinfunction "VCC_3") (pintype "bidirectional"))
    )
    (net (code "41") (name "PANEL_CURRENT") (class "Default")
      (node (ref "U3") (pin "23") (pinfunction "PC0(ADC0)_23") (pintype "bidirectional"))
      (node (ref "U4") (pin "2") (pinfunction "OUT_2") (pintype "bidirectional"))
    )
    (net (code "42") (name "PANEL_EN") (class "Default")
      (node (ref "R22") (pin "2") (pinfunction "2_2") (pintype "passive"))
      (node (ref "U3") (pin "9") (pinfunction "PD5(T1)_9") (pintype "bidirectional"))
    )
    (net (code "43") (name "PANEL_SWITCH") (class "Default")
      (node (ref "R7") (pin "1") (pinfunction "1_1") (pintype "passive"))
      (node (ref "RSENSE") (pin "2") (pinfunction "2_2") (pintype "passive"))
      (node (ref "U5") (pin "D") (pinfunction "D_D") (pintype "bidirectional"))
    )
    (net (code "44") (name "PANEL_VOLTAGE") (class "Default")
      (node (ref "C14") (pin "2") (pinfunction "2_2") (pintype "passive"))
      (node (ref "R26") (pin "1") (pinfunction "1_1") (pintype "passive"))
      (node (ref "R27") (pin "2") (pinfunction "2_2") (pintype "passive"))
      (node (ref "U3") (pin "24") (pinfunction "PC1(ADC1)_24") (pintype "bidirectional"))
    )
    (net (code "45") (name "PWRKEY") (class "Default")
      (node (ref "Q7") (pin "3") (pinfunction "C_3") (pintype "passive"))
      (node (ref "U2") (pin "1") (pinfunction "PWRKEY_1") (pintype "input"))
    )
    (net (code "46") (name "RSENSE+") (class "Default")
      (node (ref "C10") (pin "1") (pinfunction "1_1") (pintype "passive"))
      (node (ref "R7") (pin "2") (pinfunction "2_2") (pintype "passive"))
      (node (ref "U4") (pin "4") (pinfunction "RSENSE+_4") (pintype "bidirectional"))
    )
    (net (code "47") (name "RSENSE-") (class "Default")
      (node (ref "C12") (pin "1") (pinfunction "1_1") (pintype "passive"))
      (node (ref "R11") (pin "2") (pinfunction "2_2") (pintype "passive"))
      (node (ref "U4") (pin "5") (pinfunction "RSENSE-_5") (pintype "bidirectional"))
    )
    (net (code "48") (name "RST") (class "Default")
      (node (ref "C8") (pin "1") (pinfunction "1_1") (pintype "passive"))
      (node (ref "R3") (pin "1") (pinfunction "1_1") (pintype "passive"))
      (node (ref "RST") (pin "TP") (pinfunction "TP_TP") (pintype "input"))
      (node (ref "U3") (pin "29") (pinfunction "PC6(/RESET)_29") (pintype "bidirectional"))
    )
    (net (code "49") (name "RX") (class "Default")
      (node (ref "RX") (pin "TP") (pinfunction "TP_TP") (pintype "input"))
      (node (ref "TTL") (pin "3") (pinfunction "3_3") (pintype "passive"))
      (node (ref "U3") (pin "30") (pinfunction "PD0(RXD)_30") (pintype "bidirectional"))
    )
    (net (code "50") (name "SCK") (class "Default")
      (node (ref "SCK") (pin "TP") (pinfunction "TP_TP") (pintype "input"))
      (node (ref "U3") (pin "17") (pinfunction "PB5(SCK)_17") (pintype "bidirectional"))
    )
    (net (code "51") (name "SIM_CLK") (class "Default")
      (node (ref "R18") (pin "2") (pinfunction "2_2") (pintype "passive"))
      (node (ref "U2") (pin "32") (pinfunction "SIM_CLK_32") (pintype "output"))
    )
    (net (code "52") (name "SIM_CLK_DIRECT") (class "Default")
      (node (ref "R18") (pin "1") (pinfunction "1_1") (pintype "passive"))
      (node (ref "SIMHOLDER") (pin "3") (pinfunction "CLK_3") (pintype "bidirectional"))
      (node (ref "VCC1") (pin "TP") (pinfunction "TP_TP") (pintype "input"))
    )
    (net (code "53") (name "SIM_DATA") (class "Default")
      (node (ref "R19") (pin "1") (pinfunction "1_1") (pintype "passive"))
      (node (ref "U2") (pin "31") (pinfunction "SIM_DATA_31") (pintype "bidirectional"))
    )
    (net (code "54") (name "SIM_DATA_DIRECT") (class "Default")
      (node (ref "GND11") (pin "TP") (pinfunction "TP_TP") (pintype "input"))
      (node (ref "R19") (pin "2") (pinfunction "2_2") (pintype "passive"))
      (node (ref "SIMHOLDER") (pin "4") (pinfunction "I/O_4") (pintype "bidirectional"))
    )
    (net (code "55") (name "SIM_RST") (class "Default")
      (node (ref "R17") (pin "2") (pinfunction "2_2") (pintype "passive"))
      (node (ref "U2") (pin "33") (pinfunction "SIM_RST_33") (pintype "output"))
    )
    (net (code "56") (name "SIM_RST_DIRECT") (class "Default")
      (node (ref "R17") (pin "1") (pinfunction "1_1") (pintype "passive"))
      (node (ref "SCK1") (pin "TP") (pinfunction "TP_TP") (pintype "input"))
      (node (ref "SIMHOLDER") (pin "2") (pinfunction "RST_2") (pintype "bidirectional"))
    )
    (net (code "57") (name "SIM_VDD") (class "Default")
      (node (ref "C20") (pin "1") (pinfunction "1_1") (pintype "passive"))
      (node (ref "RST1") (pin "TP") (pinfunction "TP_TP") (pintype "input"))
      (node (ref "SIMHOLDER") (pin "1") (pinfunction "VCC_1") (pintype "bidirectional"))
      (node (ref "U2") (pin "30") (pinfunction "SIM_VDD_30") (pintype "output"))
    )
    (net (code "58") (name "STATUS") (class "Default")
      (node (ref "R20") (pin "2") (pinfunction "2_2") (pintype "passive"))
      (node (ref "U2") (pin "66") (pinfunction "STATUS_66") (pintype "output"))
      (node (ref "U3") (pin "10") (pinfunction "PD6(AIN0)_10") (pintype "bidirectional"))
    )
    (net (code "59") (name "TX") (class "Default")
      (node (ref "TTL") (pin "2") (pinfunction "2_2") (pintype "passive"))
      (node (ref "TX") (pin "TP") (pinfunction "TP_TP") (pintype "input"))
      (node (ref "U3") (pin "31") (pinfunction "PD1(TXD)_31") (pintype "bidirectional"))
    )
    (net (code "60") (name "VCC") (class "Default")
      (node (ref "C17") (pin "2") (pinfunction "2_2") (pintype "passive"))
      (node (ref "C18") (pin "2") (pinfunction "2_2") (pintype "passive"))
      (node (ref "C19") (pin "2") (pinfunction "2_2") (pintype "passive"))
      (node (ref "C2") (pin "+") (pinfunction "+_+") (pintype "passive"))
      (node (ref "C21") (pin "2") (pinfunction "2_2") (pintype "passive"))
      (node (ref "C22") (pin "2") (pinfunction "2_2") (pintype "passive"))
      (node (ref "C3") (pin "+") (pinfunction "+_+") (pintype "passive"))
      (node (ref "C4") (pin "2") (pinfunction "2_2") (pintype "passive"))
      (node (ref "C5") (pin "2") (pinfunction "2_2") (pintype "passive"))
      (node (ref "C7") (pin "2") (pinfunction "2_2") (pintype "passive"))
      (node (ref "C9") (pin "2") (pinfunction "2_2") (pintype "passive"))
      (node (ref "L1") (pin "2") (pinfunction "2_2") (pintype "passive"))
      (node (ref "NETLIGHT") (pin "+") (pinfunction "+_+") (pintype "passive"))
      (node (ref "POWER") (pin "+") (pinfunction "+_+") (pintype "passive"))
      (node (ref "R3") (pin "2") (pinfunction "2_2") (pintype "passive"))
      (node (ref "R6") (pin "2") (pinfunction "2_2") (pintype "passive"))
      (node (ref "STATUS") (pin "+") (pinfunction "+_+") (pintype "passive"))
      (node (ref "TTL") (pin "4") (pinfunction "4_4") (pintype "passive"))
      (node (ref "U2") (pin "55") (pinfunction "VBAT_55") (pintype "power_in"))
      (node (ref "U2") (pin "56") (pinfunction "VBAT_56") (pintype "power_in"))
      (node (ref "U2") (pin "57") (pinfunction "VBAT_57") (pintype "power_in"))
      (node (ref "U3") (pin "18") (pinfunction "AVCC_18") (pintype "bidirectional"))
      (node (ref "U3") (pin "20") (pinfunction "AREF_20") (pintype "bidirectional"))
      (node (ref "U3") (pin "4") (pinfunction "VCC_4") (pintype "bidirectional"))
      (node (ref "U3") (pin "6") (pinfunction "VCC_6") (pintype "bidirectional"))
      (node (ref "VCC") (pin "TP") (pinfunction "TP_TP") (pintype "input"))
    )
    (net (code "61") (name "VDD") (class "Default")
      (node (ref "C11") (pin "2") (pinfunction "2_2") (pintype "passive"))
      (node (ref "C24") (pin "2") (pinfunction "2_2") (pintype "passive"))
      (node (ref "D2") (pin "C") (pinfunction "C_C") (pintype "passive"))
      (node (ref "R4") (pin "2") (pinfunction "2_2") (pintype "passive"))
      (node (ref "U1") (pin "2") (pinfunction "VIN_2") (pintype "input"))
    )
    (net (code "62") (name "VRTC") (class "Default")
      (node (ref "C15") (pin "+") (pinfunction "+_+") (pintype "passive"))
      (node (ref "U2") (pin "26") (pinfunction "VRTC_26") (pintype "bidirectional"))
    )
    (net (code "63") (name "unconnected-(SIMHOLDER-VPP-Pad5)") (class "Default")
      (node (ref "SIMHOLDER") (pin "5") (pinfunction "VPP_5") (pintype "bidirectional"))
    )
    (net (code "64") (name "unconnected-(U1-NC-Pad1)") (class "Default")
      (node (ref "U1") (pin "1") (pinfunction "NC_1") (pintype "no_connect"))
    )
    (net (code "65") (name "unconnected-(U1-NC-Pad6)") (class "Default")
      (node (ref "U1") (pin "6") (pinfunction "NC_6") (pintype "no_connect"))
    )
    (net (code "66") (name "unconnected-(U1-NC-Pad8)") (class "Default")
      (node (ref "U1") (pin "8") (pinfunction "NC_8") (pintype "no_connect"))
    )
    (net (code "67") (name "unconnected-(U2-ADC-Pad25)") (class "Default")
      (node (ref "U2") (pin "25") (pinfunction "ADC_25") (pintype "input"))
    )
    (net (code "68") (name "unconnected-(U2-CTS-Pad7)") (class "Default")
      (node (ref "U2") (pin "7") (pinfunction "CTS_7") (pintype "output"))
    )
    (net (code "69") (name "unconnected-(U2-DBG_RXD-Pad28)") (class "Default")
      (node (ref "U2") (pin "28") (pinfunction "DBG_RXD_28") (pintype "input"))
    )
    (net (code "70") (name "unconnected-(U2-DBG_TXD-Pad27)") (class "Default")
      (node (ref "U2") (pin "27") (pinfunction "DBG_TXD_27") (pintype "output"))
    )
    (net (code "71") (name "unconnected-(U2-DCD-Pad5)") (class "Default")
      (node (ref "U2") (pin "5") (pinfunction "DCD_5") (pintype "output"))
    )
    (net (code "72") (name "unconnected-(U2-DISP_CLK-Pad11)") (class "Default")
      (node (ref "U2") (pin "11") (pinfunction "DISP_CLK_11") (pintype "output"))
    )
    (net (code "73") (name "unconnected-(U2-DISP_CS-Pad14)") (class "Default")
      (node (ref "U2") (pin "14") (pinfunction "DISP_CS_14") (pintype "output"))
    )
    (net (code "74") (name "unconnected-(U2-DISP_DATA-Pad12)") (class "Default")
      (node (ref "U2") (pin "12") (pinfunction "DISP_DATA_12") (pintype "bidirectional"))
    )
    (net (code "75") (name "unconnected-(U2-DISP_D{slash}C-Pad13)") (class "Default")
      (node (ref "U2") (pin "13") (pinfunction "DISP_D/C_13") (pintype "output"))
    )
    (net (code "76") (name "unconnected-(U2-DSR-Pad6)") (class "Default")
      (node (ref "U2") (pin "6") (pinfunction "DSR_6") (pintype "output"))
    )
    (net (code "77") (name "unconnected-(U2-DTR-Pad3)") (class "Default")
      (node (ref "U2") (pin "3") (pinfunction "DTR_3") (pintype "input"))
    )
    (net (code "78") (name "unconnected-(U2-GPIO1{slash}KBR4-Pad40)") (class "Default")
      (node (ref "U2") (pin "40") (pinfunction "GPIO1/KBR4_40") (pintype "output"))
    )
    (net (code "79") (name "unconnected-(U2-GPIO2{slash}KBR3-Pad41)") (class "Default")
      (node (ref "U2") (pin "41") (pinfunction "GPIO2/KBR3_41") (pintype "output"))
    )
    (net (code "80") (name "unconnected-(U2-GPIO3{slash}KBR2-Pad42)") (class "Default")
      (node (ref "U2") (pin "42") (pinfunction "GPIO3/KBR2_42") (pintype "output"))
    )
    (net (code "81") (name "unconnected-(U2-GPIO4{slash}KBR1-Pad43)") (class "Default")
      (node (ref "U2") (pin "43") (pinfunction "GPIO4/KBR1_43") (pintype "output"))
    )
    (net (code "82") (name "unconnected-(U2-GPIO5{slash}KBR0-Pad44)") (class "Default")
      (node (ref "U2") (pin "44") (pinfunction "GPIO5/KBR0_44") (pintype "output"))
    )
    (net (code "83") (name "unconnected-(U2-GPIO6{slash}KBC4-Pad47)") (class "Default")
      (node (ref "U2") (pin "47") (pinfunction "GPIO6/KBC4_47") (pintype "input"))
    )
    (net (code "84") (name "unconnected-(U2-GPIO7{slash}KBC3-Pad48)") (class "Default")
      (node (ref "U2") (pin "48") (pinfunction "GPIO7/KBC3_48") (pintype "bidirectional"))
    )
    (net (code "85") (name "unconnected-(U2-GPIO8{slash}KBC2-Pad49)") (class "Default")
      (node (ref "U2") (pin "49") (pinfunction "GPIO8/KBC2_49") (pintype "input"))
    )
    (net (code "86") (name "unconnected-(U2-GPIO9{slash}KBC1-Pad50)") (class "Default")
      (node (ref "U2") (pin "50") (pinfunction "GPIO9/KBC1_50") (pintype "input"))
    )
    (net (code "87") (name "unconnected-(U2-GPIO10{slash}KBC0-Pad51)") (class "Default")
      (node (ref "U2") (pin "51") (pinfunction "GPIO10/KBC0_51") (pintype "bidirectional"))
    )
    (net (code "88") (name "unconnected-(U2-GPIO11-Pad67)") (class "Default")
      (node (ref "U2") (pin "67") (pinfunction "GPIO11_67") (pintype "bidirectional"))
    )
    (net (code "89") (name "unconnected-(U2-GPIO12-Pad68)") (class "Default")
      (node (ref "U2") (pin "68") (pinfunction "GPIO12_68") (pintype "bidirectional"))
    )
    (net (code "90") (name "unconnected-(U2-LINEIN_L-Pad24)") (class "Default")
      (node (ref "U2") (pin "24") (pinfunction "LINEIN_L_24") (pintype "input"))
    )
    (net (code "91") (name "unconnected-(U2-LINEIN_R-Pad23)") (class "Default")
      (node (ref "U2") (pin "23") (pinfunction "LINEIN_R_23") (pintype "input"))
    )
    (net (code "92") (name "unconnected-(U2-MIC_N-Pad20)") (class "Default")
      (node (ref "U2") (pin "20") (pinfunction "MIC_N_20") (pintype "input"))
    )
    (net (code "93") (name "unconnected-(U2-MIC_P-Pad19)") (class "Default")
      (node (ref "U2") (pin "19") (pinfunction "MIC_P_19") (pintype "input"))
    )
    (net (code "94") (name "unconnected-(U2-NRESET-Pad16)") (class "Default")
      (node (ref "U2") (pin "16") (pinfunction "NRESET_16") (pintype "input"))
    )
    (net (code "95") (name "unconnected-(U2-PWM1-Pad35)") (class "Default")
      (node (ref "U2") (pin "35") (pinfunction "PWM1_35") (pintype "output"))
    )
    (net (code "96") (name "unconnected-(U2-PWM2-Pad36)") (class "Default")
      (node (ref "U2") (pin "36") (pinfunction "PWM2_36") (pintype "output"))
    )
    (net (code "97") (name "unconnected-(U2-PWRKEY_OUT-Pad2)") (class "Default")
      (node (ref "U2") (pin "2") (pinfunction "PWRKEY_OUT_2") (pintype "output"))
    )
    (net (code "98") (name "unconnected-(U2-RI-Pad4)") (class "Default")
      (node (ref "U2") (pin "4") (pinfunction "RI_4") (pintype "output"))
    )
    (net (code "99") (name "unconnected-(U2-RTS-Pad8)") (class "Default")
      (node (ref "U2") (pin "8") (pinfunction "RTS_8") (pintype "input"))
    )
    (net (code "100") (name "unconnected-(U2-SCL-Pad38)") (class "Default")
      (node (ref "U2") (pin "38") (pinfunction "SCL_38") (pintype "output"))
    )
    (net (code "101") (name "unconnected-(U2-SDA-Pad37)") (class "Default")
      (node (ref "U2") (pin "37") (pinfunction "SDA_37") (pintype "bidirectional"))
    )
    (net (code "102") (name "unconnected-(U2-SIM_PRESENCE-Pad34)") (class "Default")
      (node (ref "U2") (pin "34") (pinfunction "SIM_PRESENCE_34") (pintype "input"))
    )
    (net (code "103") (name "unconnected-(U2-SPK_N-Pad22)") (class "Default")
      (node (ref "U2") (pin "22") (pinfunction "SPK_N_22") (pintype "output"))
    )
    (net (code "104") (name "unconnected-(U2-SPK_P-Pad21)") (class "Default")
      (node (ref "U2") (pin "21") (pinfunction "SPK_P_21") (pintype "output"))
    )
    (net (code "105") (name "unconnected-(U2-VDD_EXT-Pad15)") (class "Default")
      (node (ref "U2") (pin "15") (pinfunction "VDD_EXT_15") (pintype "output"))
    )
    (net (code "106") (name "unconnected-(U3-ADC6-Pad19)") (class "Default")
      (node (ref "U3") (pin "19") (pinfunction "ADC6_19") (pintype "bidirectional"))
    )
    (net (code "107") (name "unconnected-(U3-ADC7-Pad22)") (class "Default")
      (node (ref "U3") (pin "22") (pinfunction "ADC7_22") (pintype "bidirectional"))
    )
    (net (code "108") (name "unconnected-(U3-PB0(ICP)-Pad12)") (class "Default")
      (node (ref "U3") (pin "12") (pinfunction "PB0(ICP)_12") (pintype "bidirectional"))
    )
    (net (code "109") (name "unconnected-(U3-PB1(OC1A)-Pad13)") (class "Default")
      (node (ref "U3") (pin "13") (pinfunction "PB1(OC1A)_13") (pintype "bidirectional"))
    )
  )
)
